# QSPI.net
KiCad netlist of a schematic drawn in Altium Designer
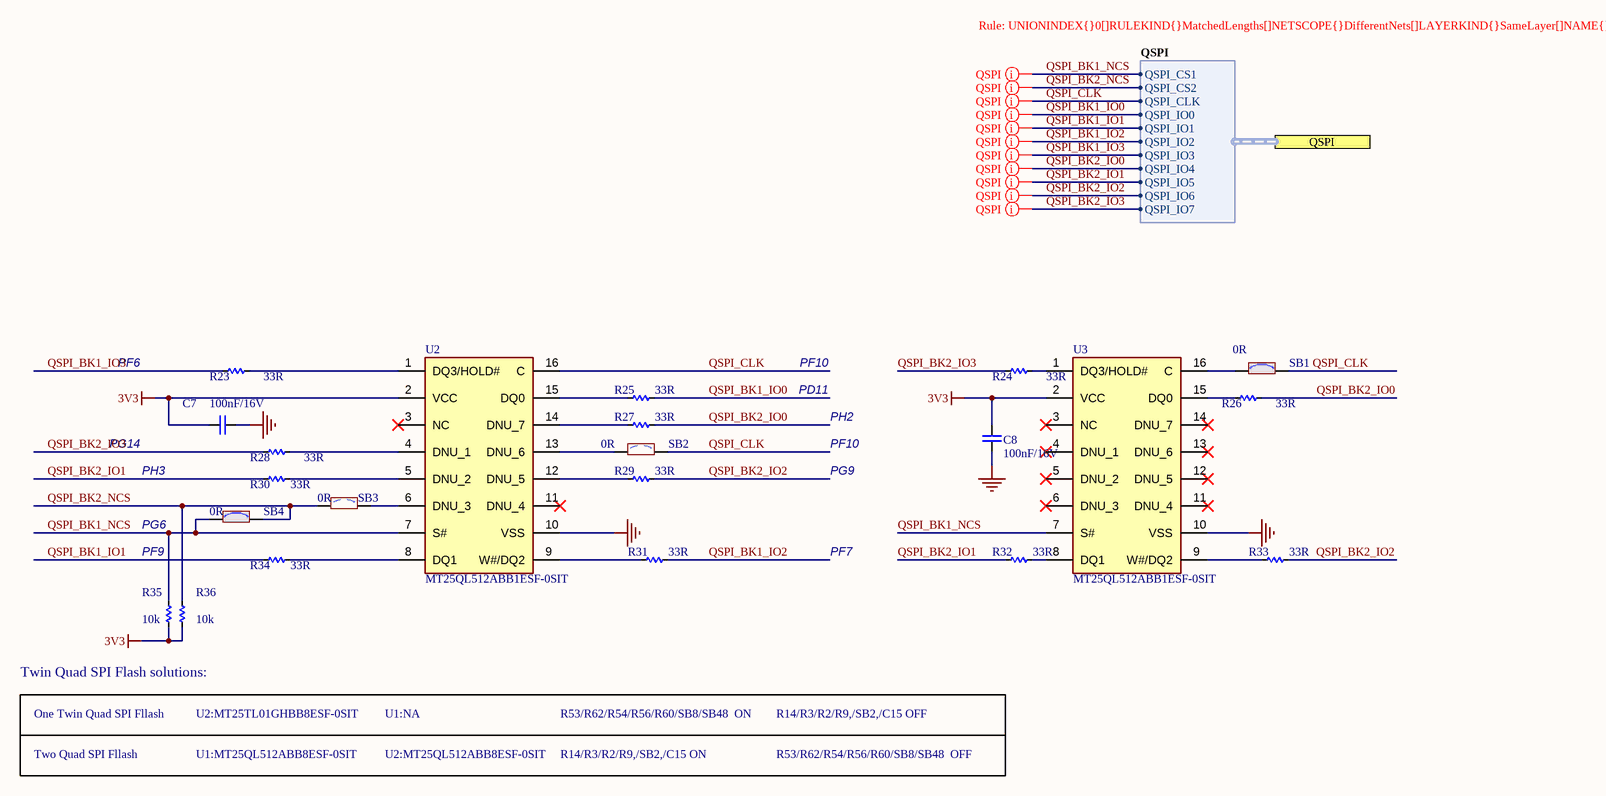
[diagram p0: QSPI.SchDoc]

(export (version "E")
  (design (tool "Eeschema 10.0.6"))
  (components
    (comp (ref "C7")
      (value "100nF/16V")
      (footprint "CAP_C_1608X80")
      (description "CAP_Chip")
      (libsource (lib "LABLIB") (part "CAP_SMD"))
    )
    (comp (ref "C8")
      (value "100nF/16V")
      (footprint "CAP_C_1608X80")
      (description "CAP_Chip")
      (libsource (lib "LABLIB") (part "CAP_SMD"))
    )
    (comp (ref "R23")
      (value "33R")
      (footprint "RES_C_1608X60")
      (description "RES")
      (libsource (lib "LABLIB") (part "_RES_B_2"))
    )
    (comp (ref "R24")
      (value "33R")
      (footprint "RES_C_1608X60")
      (description "RES")
      (libsource (lib "LABLIB") (part "_RES_B_2"))
    )
    (comp (ref "R25")
      (value "33R")
      (footprint "RES_C_1608X60")
      (description "RES")
      (libsource (lib "LABLIB") (part "_RES_B_2"))
    )
    (comp (ref "R26")
      (value "33R")
      (footprint "RES_C_1608X60")
      (description "RES")
      (libsource (lib "LABLIB") (part "_RES_B_2"))
    )
    (comp (ref "R27")
      (value "33R")
      (footprint "RES_C_1608X60")
      (description "RES")
      (libsource (lib "LABLIB") (part "_RES_B_2"))
    )
    (comp (ref "R28")
      (value "33R")
      (footprint "RES_C_1608X60")
      (description "RES")
      (libsource (lib "LABLIB") (part "_RES_B_2"))
    )
    (comp (ref "R29")
      (value "33R")
      (footprint "RES_C_1608X60")
      (description "RES")
      (libsource (lib "LABLIB") (part "_RES_B_2"))
    )
    (comp (ref "R30")
      (value "33R")
      (footprint "RES_C_1608X60")
      (description "RES")
      (libsource (lib "LABLIB") (part "_RES_B_2"))
    )
    (comp (ref "R31")
      (value "33R")
      (footprint "RES_C_1608X60")
      (description "RES")
      (libsource (lib "LABLIB") (part "_RES_B_2"))
    )
    (comp (ref "R32")
      (value "33R")
      (footprint "RES_C_1608X60")
      (description "RES")
      (libsource (lib "LABLIB") (part "_RES_B_2"))
    )
    (comp (ref "R33")
      (value "33R")
      (footprint "RES_C_1608X60")
      (description "RES")
      (libsource (lib "LABLIB") (part "_RES_B_2"))
    )
    (comp (ref "R34")
      (value "33R")
      (footprint "RES_C_1608X60")
      (description "RES")
      (libsource (lib "LABLIB") (part "_RES_B_2"))
    )
    (comp (ref "R35")
      (value "10k")
      (footprint "RES_C_1608X60")
      (description "RES")
      (libsource (lib "LABLIB") (part "_RES_B_2"))
    )
    (comp (ref "R36")
      (value "10k")
      (footprint "RES_C_1608X60")
      (description "RES")
      (libsource (lib "LABLIB") (part "_RES_B_2"))
    )
    (comp (ref "SB1")
      (value "0R")
      (footprint "Jump2")
      (description "Solder Bridge ON")
      (fields
        (field (name "INTERNAL_PART_NUMBER") "MCD-00071")
        (field (name "MANUFACTURER") "YAGEO")
        (field (name "PROVIDED_BY") "Subcon")
      )
      (libsource (lib "MCD_PARTS_database") (part "SB_ON"))
    )
    (comp (ref "SB2")
      (value "0R")
      (footprint "Jump2")
      (description "Solder Bridge OFF")
      (fields (field (name "INTERNAL_PART_NUMBER") "MCD-00072") (field (name "MANUFACTURER") "YAGEO"))
      (libsource (lib "MCD_PARTS_database") (part "SB_OFF"))
    )
    (comp (ref "SB3")
      (value "0R")
      (footprint "Jump2")
      (description "Solder Bridge OFF")
      (fields (field (name "INTERNAL_PART_NUMBER") "MCD-00072") (field (name "MANUFACTURER") "YAGEO"))
      (libsource (lib "MCD_PARTS_database") (part "SB_OFF"))
    )
    (comp (ref "SB4")
      (value "0R")
      (footprint "Jump2")
      (description "Solder Bridge ON")
      (fields
        (field (name "INTERNAL_PART_NUMBER") "MCD-00071")
        (field (name "MANUFACTURER") "YAGEO")
        (field (name "PROVIDED_BY") "Subcon")
      )
      (libsource (lib "MCD_PARTS_database") (part "SB_ON"))
    )
    (comp (ref "U2")
      (value "MT25QL512ABB1ESF-0SIT")
      (footprint "SOIC127P1032X265-16N")
      (description "IC FLASH 512MBIT 133MHZ 16SO")
      (fields
        (field (name "MANUFACTURER_PART_NUMBER") "MT25QL512ABB8ESF-0SIT")
        (field (name "MOUSER PART NUMBER") "340-278183-TRAY")
      )
      (libsource (lib "COMM_SCHLIB") (part "MT25QL512ABB1ESF-0SIT"))
    )
    (comp (ref "U3")
      (value "MT25QL512ABB1ESF-0SIT")
      (footprint "SOIC127P1032X265-16N")
      (description "IC FLASH 512MBIT 133MHZ 16SO")
      (fields
        (field (name "MANUFACTURER_PART_NUMBER") "MT25QL512ABB8ESF-0SIT")
        (field (name "MOUSER PART NUMBER") "340-278183-TRAY")
      )
      (libsource (lib "COMM_SCHLIB") (part "MT25QL512ABB1ESF-0SIT"))
    )
  )
  (nets
    (net (code "2") (name "/QSPI_BK1_IO0") (class "Default")
      (node (ref "R25") (pin "2") (pinfunction "2_2") (pintype "passive"))
    )
    (net (code "3") (name "/QSPI_BK1_IO1") (class "Default")
      (node (ref "R34") (pin "1") (pinfunction "1_1") (pintype "passive"))
    )
    (net (code "4") (name "/QSPI_BK1_IO2") (class "Default")
      (node (ref "R31") (pin "2") (pinfunction "2_2") (pintype "passive"))
    )
    (net (code "5") (name "/QSPI_BK1_IO3") (class "Default")
      (node (ref "R23") (pin "1") (pinfunction "1_1") (pintype "passive"))
    )
    (net (code "6") (name "/QSPI_BK1_NCS") (class "Default")
      (node (ref "R35") (pin "2") (pinfunction "2_2") (pintype "passive"))
      (node (ref "SB4") (pin "1") (pinfunction "1_1") (pintype "passive"))
      (node (ref "U2") (pin "7") (pinfunction "S#_7") (pintype "passive"))
      (node (ref "U3") (pin "7") (pinfunction "S#_7") (pintype "passive"))
    )
    (net (code "7") (name "/QSPI_BK2_IO0") (class "Default")
      (node (ref "R26") (pin "2") (pinfunction "2_2") (pintype "passive"))
      (node (ref "R27") (pin "2") (pinfunction "2_2") (pintype "passive"))
    )
    (net (code "8") (name "/QSPI_BK2_IO1") (class "Default")
      (node (ref "R30") (pin "1") (pinfunction "1_1") (pintype "passive"))
      (node (ref "R32") (pin "1") (pinfunction "1_1") (pintype "passive"))
    )
    (net (code "9") (name "/QSPI_BK2_IO2") (class "Default")
      (node (ref "R29") (pin "2") (pinfunction "2_2") (pintype "passive"))
      (node (ref "R33") (pin "2") (pinfunction "2_2") (pintype "passive"))
    )
    (net (code "10") (name "/QSPI_BK2_IO3") (class "Default")
      (node (ref "R24") (pin "1") (pinfunction "1_1") (pintype "passive"))
      (node (ref "R28") (pin "1") (pinfunction "1_1") (pintype "passive"))
    )
    (net (code "11") (name "/QSPI_BK2_NCS") (class "Default")
      (node (ref "R36") (pin "2") (pinfunction "2_2") (pintype "passive"))
      (node (ref "SB3") (pin "1") (pinfunction "1_1") (pintype "passive"))
      (node (ref "SB4") (pin "2") (pinfunction "2_2") (pintype "passive"))
    )
    (net (code "12") (name "/QSPI_CLK") (class "Default")
      (node (ref "SB1") (pin "2") (pinfunction "2_2") (pintype "passive"))
      (node (ref "SB2") (pin "2") (pinfunction "2_2") (pintype "passive"))
      (node (ref "U2") (pin "16") (pinfunction "C_16") (pintype "passive"))
    )
    (net (code "14") (name "3V3") (class "Default")
      (node (ref "C7") (pin "2") (pinfunction "2_2") (pintype "passive"))
      (node (ref "C8") (pin "1") (pinfunction "1_1") (pintype "passive"))
      (node (ref "R35") (pin "1") (pinfunction "1_1") (pintype "passive"))
      (node (ref "R36") (pin "1") (pinfunction "1_1") (pintype "passive"))
      (node (ref "U2") (pin "2") (pinfunction "VCC_2") (pintype "passive"))
      (node (ref "U3") (pin "2") (pinfunction "VCC_2") (pintype "passive"))
    )
    (net (code "15") (name "GND") (class "Default")
      (node (ref "C7") (pin "1") (pinfunction "1_1") (pintype "passive"))
      (node (ref "C8") (pin "2") (pinfunction "2_2") (pintype "passive"))
      (node (ref "U2") (pin "10") (pinfunction "VSS_10") (pintype "passive"))
      (node (ref "U3") (pin "10") (pinfunction "VSS_10") (pintype "passive"))
    )
    (net (code "16") (name "Net-(U2-DNU_1)") (class "Default")
      (node (ref "R28") (pin "2") (pinfunction "2_2") (pintype "passive"))
      (node (ref "U2") (pin "4") (pinfunction "DNU_1_4") (pintype "passive"))
    )
    (net (code "17") (name "Net-(U2-DNU_2)") (class "Default")
      (node (ref "R30") (pin "2") (pinfunction "2_2") (pintype "passive"))
      (node (ref "U2") (pin "5") (pinfunction "DNU_2_5") (pintype "passive"))
    )
    (net (code "18") (name "Net-(U2-DNU_3)") (class "Default")
      (node (ref "SB3") (pin "2") (pinfunction "2_2") (pintype "passive"))
      (node (ref "U2") (pin "6") (pinfunction "DNU_3_6") (pintype "passive"))
    )
    (net (code "19") (name "Net-(U2-DNU_5)") (class "Default")
      (node (ref "R29") (pin "1") (pinfunction "1_1") (pintype "passive"))
      (node (ref "U2") (pin "12") (pinfunction "DNU_5_12") (pintype "passive"))
    )
    (net (code "20") (name "Net-(U2-DNU_6)") (class "Default")
      (node (ref "SB2") (pin "1") (pinfunction "1_1") (pintype "passive"))
      (node (ref "U2") (pin "13") (pinfunction "DNU_6_13") (pintype "passive"))
    )
    (net (code "21") (name "Net-(U2-DNU_7)") (class "Default")
      (node (ref "R27") (pin "1") (pinfunction "1_1") (pintype "passive"))
      (node (ref "U2") (pin "14") (pinfunction "DNU_7_14") (pintype "passive"))
    )
    (net (code "22") (name "Net-(U2-DQ0)") (class "Default")
      (node (ref "R25") (pin "1") (pinfunction "1_1") (pintype "passive"))
      (node (ref "U2") (pin "15") (pinfunction "DQ0_15") (pintype "passive"))
    )
    (net (code "23") (name "Net-(U2-DQ1)") (class "Default")
      (node (ref "R34") (pin "2") (pinfunction "2_2") (pintype "passive"))
      (node (ref "U2") (pin "8") (pinfunction "DQ1_8") (pintype "passive"))
    )
    (net (code "24") (name "Net-(U2-DQ3{slash}HOLD#)") (class "Default")
      (node (ref "R23") (pin "2") (pinfunction "2_2") (pintype "passive"))
      (node (ref "U2") (pin "1") (pinfunction "DQ3/HOLD#_1") (pintype "passive"))
    )
    (net (code "25") (name "Net-(U2-W#{slash}DQ2)") (class "Default")
      (node (ref "R31") (pin "1") (pinfunction "1_1") (pintype "passive"))
      (node (ref "U2") (pin "9") (pinfunction "W#/DQ2_9") (pintype "passive"))
    )
    (net (code "26") (name "Net-(U3-C)") (class "Default")
      (node (ref "SB1") (pin "1") (pinfunction "1_1") (pintype "passive"))
      (node (ref "U3") (pin "16") (pinfunction "C_16") (pintype "passive"))
    )
    (net (code "27") (name "Net-(U3-DQ0)") (class "Default")
      (node (ref "R26") (pin "1") (pinfunction "1_1") (pintype "passive"))
      (node (ref "U3") (pin "15") (pinfunction "DQ0_15") (pintype "passive"))
    )
    (net (code "28") (name "Net-(U3-DQ1)") (class "Default")
      (node (ref "R32") (pin "2") (pinfunction "2_2") (pintype "passive"))
      (node (ref "U3") (pin "8") (pinfunction "DQ1_8") (pintype "passive"))
    )
    (net (code "29") (name "Net-(U3-DQ3{slash}HOLD#)") (class "Default")
      (node (ref "R24") (pin "2") (pinfunction "2_2") (pintype "passive"))
      (node (ref "U3") (pin "1") (pinfunction "DQ3/HOLD#_1") (pintype "passive"))
    )
    (net (code "30") (name "Net-(U3-W#{slash}DQ2)") (class "Default")
      (node (ref "R33") (pin "1") (pinfunction "1_1") (pintype "passive"))
      (node (ref "U3") (pin "9") (pinfunction "W#/DQ2_9") (pintype "passive"))
    )
    (net (code "31") (name "unconnected-(U2-DNU_4-Pad11)") (class "Default")
      (node (ref "U2") (pin "11") (pinfunction "DNU_4_11") (pintype "passive+no_connect"))
    )
    (net (code "32") (name "unconnected-(U2-NC-Pad3)") (class "Default")
      (node (ref "U2") (pin "3") (pinfunction "NC_3") (pintype "passive+no_connect"))
    )
    (net (code "33") (name "unconnected-(U3-DNU_1-Pad4)") (class "Default")
      (node (ref "U3") (pin "4") (pinfunction "DNU_1_4") (pintype "passive+no_connect"))
    )
    (net (code "34") (name "unconnected-(U3-DNU_2-Pad5)") (class "Default")
      (node (ref "U3") (pin "5") (pinfunction "DNU_2_5") (pintype "passive+no_connect"))
    )
    (net (code "35") (name "unconnected-(U3-DNU_3-Pad6)") (class "Default")
      (node (ref "U3") (pin "6") (pinfunction "DNU_3_6") (pintype "passive+no_connect"))
    )
    (net (code "36") (name "unconnected-(U3-DNU_4-Pad11)") (class "Default")
      (node (ref "U3") (pin "11") (pinfunction "DNU_4_11") (pintype "passive+no_connect"))
    )
    (net (code "37") (name "unconnected-(U3-DNU_5-Pad12)") (class "Default")
      (node (ref "U3") (pin "12") (pinfunction "DNU_5_12") (pintype "passive+no_connect"))
    )
    (net (code "38") (name "unconnected-(U3-DNU_6-Pad13)") (class "Default")
      (node (ref "U3") (pin "13") (pinfunction "DNU_6_13") (pintype "passive+no_connect"))
    )
    (net (code "39") (name "unconnected-(U3-DNU_7-Pad14)") (class "Default")
      (node (ref "U3") (pin "14") (pinfunction "DNU_7_14") (pintype "passive+no_connect"))
    )
    (net (code "40") (name "unconnected-(U3-NC-Pad3)") (class "Default")
      (node (ref "U3") (pin "3") (pinfunction "NC_3") (pintype "passive+no_connect"))
    )
  )
)
